# USBPowerSupply.net
KiCad netlist of a schematic drawn in EAGLE
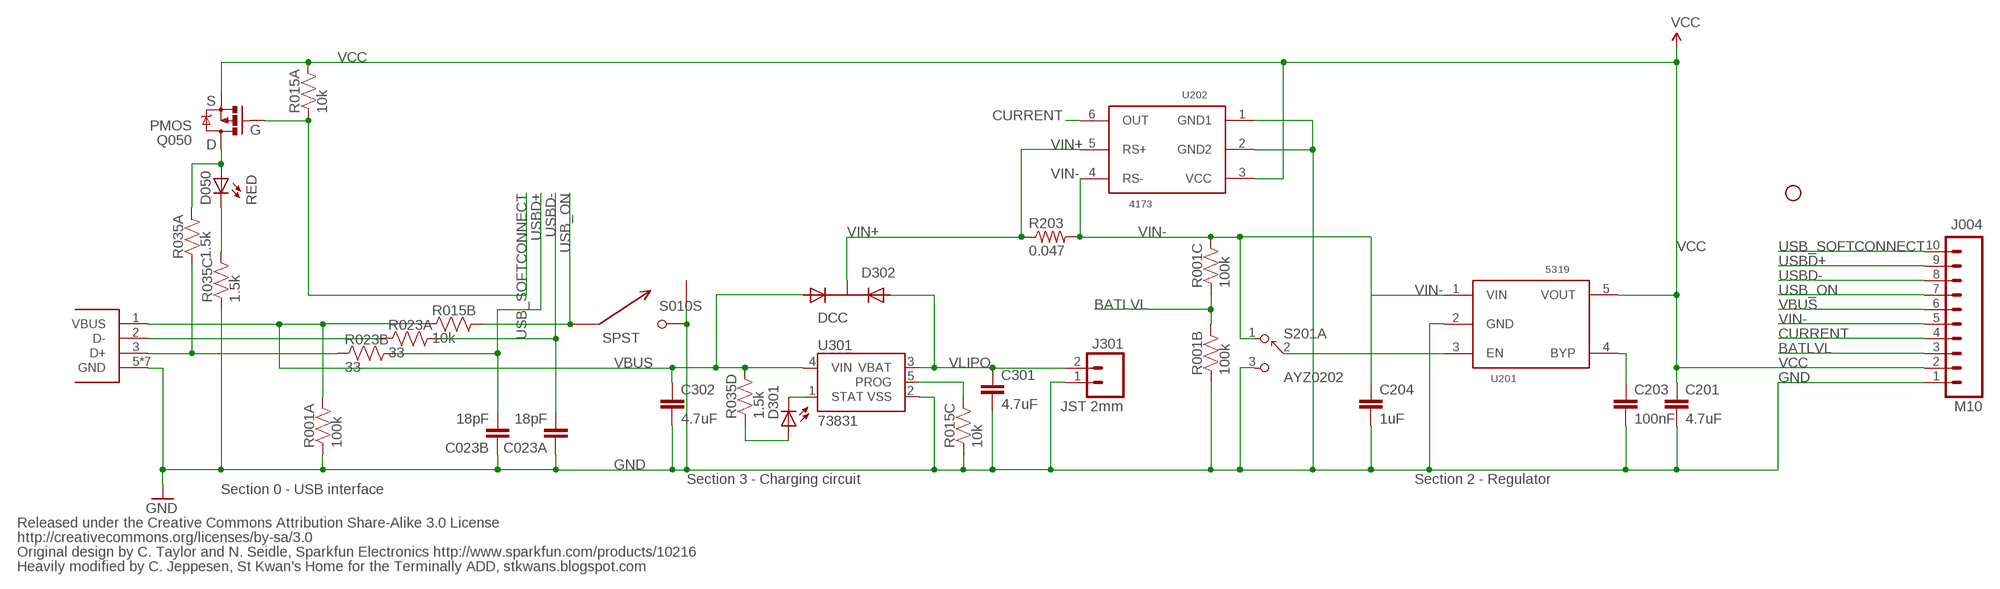
[diagram p0: schematic, sheet 1]

(export (version "E")
  (design (tool "Eeschema 10.0.6"))
  (components
    (comp (ref "C023")
      (value "18pF")
      (footprint "eagle-import:CKCM25")
      (libsource (lib "eagle-import") (part "CKCM25"))
    )
    (comp (ref "C201")
      (value "4.7uF")
      (footprint "eagle-import:0402-CAP")
      (libsource (lib "eagle-import") (part "CAP0402-CAP"))
    )
    (comp (ref "C203")
      (value "100nF")
      (footprint "eagle-import:0402-CAP")
      (libsource (lib "eagle-import") (part "CAP0402-CAP"))
    )
    (comp (ref "C204")
      (value "1uF")
      (footprint "eagle-import:0402-CAP")
      (libsource (lib "eagle-import") (part "CAP0402-CAP"))
    )
    (comp (ref "C301")
      (value "4.7uF")
      (footprint "eagle-import:0402-CAP")
      (libsource (lib "eagle-import") (part "CAP0402-CAP"))
    )
    (comp (ref "C302")
      (value "4.7uF")
      (footprint "eagle-import:0402-CAP")
      (libsource (lib "eagle-import") (part "CAP0402-CAP"))
    )
    (comp (ref "D050")
      (value "RED")
      (footprint "eagle-import:LED-0603")
      (libsource (lib "eagle-import") (part "LED0603"))
    )
    (comp (ref "D301")
      (value "RED")
      (footprint "eagle-import:LED-0603")
      (libsource (lib "eagle-import") (part "LED0603"))
    )
    (comp (ref "D302")
      (value "DCC")
      (footprint "eagle-import:SOT-23-3")
      (libsource (lib "eagle-import") (part "PMEG2005CT"))
    )
    (comp (ref "J001")
      (value "USB_MICROB_JSTGCT")
      (footprint "eagle-import:USB_MICROB_3075")
      (libsource (lib "eagle-import") (part "USB_MICROB_JSTGCT"))
    )
    (comp (ref "J004")
      (value "M10")
      (footprint "eagle-import:1X10")
      (libsource (lib "eagle-import") (part "M10{dblquote}"))
    )
    (comp (ref "J301")
      (value "JST 2mm")
      (footprint "eagle-import:JST-2-SMD")
      (libsource (lib "eagle-import") (part "M02-JST-2MM-SMT"))
    )
    (comp (ref "JP1")
      (value "STAND-OFF")
      (footprint "eagle-import:STAND-OFF")
      (libsource (lib "eagle-import") (part "STAND-OFF"))
    )
    (comp (ref "Q050")
      (value "PMOS")
      (footprint "eagle-import:SOT23-3")
      (libsource (lib "eagle-import") (part "MOSFET-PCHANNELSMD"))
    )
    (comp (ref "R001")
      (value "100k")
      (footprint "eagle-import:CRA04")
      (libsource (lib "eagle-import") (part "RP404"))
    )
    (comp (ref "R015")
      (value "10k")
      (footprint "eagle-import:CRA04")
      (libsource (lib "eagle-import") (part "RP404"))
    )
    (comp (ref "R023")
      (value "33")
      (footprint "eagle-import:CRA02")
      (libsource (lib "eagle-import") (part "RP2EXB24V"))
    )
    (comp (ref "R035")
      (value "1.5k")
      (footprint "eagle-import:CRA04")
      (libsource (lib "eagle-import") (part "RP404"))
    )
    (comp (ref "R203")
      (value "0.047")
      (footprint "eagle-import:0402-RES")
      (libsource (lib "eagle-import") (part "RESISTOR0402-RES"))
    )
    (comp (ref "S010")
      (value "SPST")
      (footprint "eagle-import:B3U-1100P")
      (libsource (lib "eagle-import") (part "B3U-1100P"))
    )
    (comp (ref "S201")
      (value "AYZ0202")
      (footprint "eagle-import:AYZ0202")
      (libsource (lib "eagle-import") (part "AYZ0202"))
    )
    (comp (ref "U201")
      (value "5319")
      (footprint "eagle-import:SOT-23-5")
      (libsource (lib "eagle-import") (part "MIC5319D5"))
    )
    (comp (ref "U202")
      (value "4173")
      (footprint "eagle-import:SOT-23-6")
      (libsource (lib "eagle-import") (part "MAX4173"))
    )
    (comp (ref "U301")
      (value "73831")
      (footprint "eagle-import:SOT23-5")
      (libsource (lib "eagle-import") (part "MCP73831"))
    )
  )
  (nets
    (net (code "1") (name "/BATLVL") (class "Default")
      (node (ref "J004") (pin "3") (pinfunction "3_3") (pintype "passive"))
      (node (ref "R001") (pin "3") (pinfunction "1_3") (pintype "passive"))
      (node (ref "R001") (pin "7") (pinfunction "2_7") (pintype "passive"))
    )
    (net (code "2") (name "/CURRENT") (class "Default")
      (node (ref "J004") (pin "4") (pinfunction "4_4") (pintype "passive"))
      (node (ref "U202") (pin "6") (pinfunction "OUT_6") (pintype "bidirectional"))
    )
    (net (code "3") (name "/USBD+") (class "Default")
      (node (ref "C023") (pin "3") (pinfunction "2_3") (pintype "passive"))
      (node (ref "J004") (pin "9") (pinfunction "9_9") (pintype "passive"))
      (node (ref "R023") (pin "3") (pinfunction "2_3") (pintype "passive"))
    )
    (net (code "4") (name "/USBD-") (class "Default")
      (node (ref "C023") (pin "4") (pinfunction "2_4") (pintype "passive"))
      (node (ref "J004") (pin "8") (pinfunction "8_8") (pintype "passive"))
      (node (ref "R023") (pin "4") (pinfunction "2_4") (pintype "passive"))
    )
    (net (code "5") (name "/USB_ON") (class "Default")
      (node (ref "J004") (pin "7") (pinfunction "7_7") (pintype "passive"))
      (node (ref "R015") (pin "7") (pinfunction "2_7") (pintype "passive"))
      (node (ref "S010") (pin "P$1") (pinfunction "1_P$1") (pintype "bidirectional"))
    )
    (net (code "6") (name "/USB_SOFTCONNECT") (class "Default")
      (node (ref "J004") (pin "10") (pinfunction "10_10") (pintype "passive"))
      (node (ref "Q050") (pin "1") (pinfunction "G_1") (pintype "passive"))
      (node (ref "R015") (pin "1") (pinfunction "1_1") (pintype "passive"))
    )
    (net (code "7") (name "/VBUS") (class "Default")
      (node (ref "C302") (pin "1") (pinfunction "1_1") (pintype "passive"))
      (node (ref "D302") (pin "1") (pinfunction "A1_1") (pintype "passive"))
      (node (ref "J001") (pin "1") (pinfunction "VBUS_1") (pintype "bidirectional"))
      (node (ref "J004") (pin "6") (pinfunction "6_6") (pintype "passive"))
      (node (ref "R001") (pin "8") (pinfunction "2_8") (pintype "passive"))
      (node (ref "R015") (pin "2") (pinfunction "1_2") (pintype "passive"))
      (node (ref "R035") (pin "5") (pinfunction "2_5") (pintype "passive"))
      (node (ref "U301") (pin "4") (pinfunction "VIN_4") (pintype "power_in"))
    )
    (net (code "8") (name "/VIN+") (class "Default")
      (node (ref "D302") (pin "3") (pinfunction "K_3") (pintype "passive"))
      (node (ref "R203") (pin "1") (pinfunction "1_1") (pintype "passive"))
      (node (ref "U202") (pin "5") (pinfunction "RS+_5") (pintype "bidirectional"))
    )
    (net (code "9") (name "/VIN-") (class "Default")
      (node (ref "C204") (pin "1") (pinfunction "1_1") (pintype "passive"))
      (node (ref "J004") (pin "5") (pinfunction "5_5") (pintype "passive"))
      (node (ref "R001") (pin "6") (pinfunction "2_6") (pintype "passive"))
      (node (ref "R203") (pin "2") (pinfunction "2_2") (pintype "passive"))
      (node (ref "S201") (pin "1") (pinfunction "P$1_1") (pintype "bidirectional"))
      (node (ref "U201") (pin "1") (pinfunction "VIN_1") (pintype "bidirectional"))
      (node (ref "U202") (pin "4") (pinfunction "RS-_4") (pintype "bidirectional"))
    )
    (net (code "10") (name "/VLIPO") (class "Default")
      (node (ref "C301") (pin "1") (pinfunction "1_1") (pintype "passive"))
      (node (ref "D302") (pin "2") (pinfunction "A2_2") (pintype "passive"))
      (node (ref "J301") (pin "2") (pinfunction "2_2") (pintype "passive"))
      (node (ref "U301") (pin "3") (pinfunction "VBAT_3") (pintype "power_in"))
    )
    (net (code "11") (name "GND") (class "Default")
      (node (ref "C023") (pin "1") (pinfunction "1_1") (pintype "passive"))
      (node (ref "C023") (pin "2") (pinfunction "1_2") (pintype "passive"))
      (node (ref "C201") (pin "2") (pinfunction "2_2") (pintype "passive"))
      (node (ref "C203") (pin "2") (pinfunction "2_2") (pintype "passive"))
      (node (ref "C204") (pin "2") (pinfunction "2_2") (pintype "passive"))
      (node (ref "C301") (pin "2") (pinfunction "2_2") (pintype "passive"))
      (node (ref "C302") (pin "2") (pinfunction "2_2") (pintype "passive"))
      (node (ref "J001") (pin "5") (pinfunction "GND_5") (pintype "bidirectional"))
      (node (ref "J001") (pin "P$1") (pinfunction "GND_P$1") (pintype "bidirectional"))
      (node (ref "J001") (pin "P$10") (pinfunction "GND_P$10") (pintype "bidirectional"))
      (node (ref "J001") (pin "P$2") (pinfunction "GND_P$2") (pintype "bidirectional"))
      (node (ref "J001") (pin "P$3") (pinfunction "GND_P$3") (pintype "bidirectional"))
      (node (ref "J001") (pin "P$4") (pinfunction "GND_P$4") (pintype "bidirectional"))
      (node (ref "J001") (pin "P$8") (pinfunction "GND_P$8") (pintype "bidirectional"))
      (node (ref "J004") (pin "1") (pinfunction "1_1") (pintype "passive"))
      (node (ref "J301") (pin "1") (pinfunction "1_1") (pintype "passive"))
      (node (ref "R001") (pin "1") (pinfunction "1_1") (pintype "passive"))
      (node (ref "R001") (pin "2") (pinfunction "1_2") (pintype "passive"))
      (node (ref "R015") (pin "3") (pinfunction "1_3") (pintype "passive"))
      (node (ref "R035") (pin "3") (pinfunction "1_3") (pintype "passive"))
      (node (ref "S010") (pin "P$2") (pinfunction "2_P$2") (pintype "bidirectional"))
      (node (ref "S010") (pin "P$3") (pinfunction "1_P$3") (pintype "bidirectional"))
      (node (ref "S201") (pin "3") (pinfunction "P$2_3") (pintype "bidirectional"))
      (node (ref "U201") (pin "2") (pinfunction "GND_2") (pintype "bidirectional"))
      (node (ref "U202") (pin "1") (pinfunction "GND1_1") (pintype "bidirectional"))
      (node (ref "U202") (pin "2") (pinfunction "GND2_2") (pintype "bidirectional"))
      (node (ref "U301") (pin "2") (pinfunction "VSS_2") (pintype "power_in"))
    )
    (net (code "12") (name "Net-(J001-D+)") (class "Default")
      (node (ref "J001") (pin "3") (pinfunction "D+_3") (pintype "bidirectional"))
      (node (ref "R023") (pin "2") (pinfunction "1_2") (pintype "passive"))
      (node (ref "R035") (pin "1") (pinfunction "1_1") (pintype "passive"))
    )
    (net (code "13") (name "Net-(J001-D-)") (class "Default")
      (node (ref "J001") (pin "2") (pinfunction "D-_2") (pintype "bidirectional"))
      (node (ref "R023") (pin "1") (pinfunction "1_1") (pintype "passive"))
    )
    (net (code "14") (name "Net-(Q050-D)") (class "Default")
      (node (ref "D050") (pin "A") (pinfunction "A_A") (pintype "passive"))
      (node (ref "Q050") (pin "3") (pinfunction "D_3") (pintype "passive"))
      (node (ref "R035") (pin "8") (pinfunction "2_8") (pintype "passive"))
    )
    (net (code "15") (name "Net-(R015C-2)") (class "Default")
      (node (ref "R015") (pin "6") (pinfunction "2_6") (pintype "passive"))
      (node (ref "U301") (pin "5") (pinfunction "PROG_5") (pintype "input"))
    )
    (net (code "16") (name "Net-(R035C-2)") (class "Default")
      (node (ref "D050") (pin "C") (pinfunction "C_C") (pintype "passive"))
      (node (ref "R035") (pin "6") (pinfunction "2_6") (pintype "passive"))
    )
    (net (code "17") (name "Net-(R035D-1)") (class "Default")
      (node (ref "D301") (pin "A") (pinfunction "A_A") (pintype "passive"))
      (node (ref "R035") (pin "4") (pinfunction "1_4") (pintype "passive"))
    )
    (net (code "18") (name "Net-(S201A-P$3)") (class "Default")
      (node (ref "S201") (pin "2") (pinfunction "P$3_2") (pintype "bidirectional"))
      (node (ref "U201") (pin "3") (pinfunction "EN_3") (pintype "bidirectional"))
    )
    (net (code "19") (name "Net-(U201-BYP)") (class "Default")
      (node (ref "C203") (pin "1") (pinfunction "1_1") (pintype "passive"))
      (node (ref "U201") (pin "4") (pinfunction "BYP_4") (pintype "bidirectional"))
    )
    (net (code "20") (name "Net-(U301-STAT)") (class "Default")
      (node (ref "D301") (pin "C") (pinfunction "C_C") (pintype "passive"))
      (node (ref "U301") (pin "1") (pinfunction "STAT_1") (pintype "output"))
    )
    (net (code "21") (name "VCC") (class "Default")
      (node (ref "C201") (pin "1") (pinfunction "1_1") (pintype "passive"))
      (node (ref "J004") (pin "2") (pinfunction "2_2") (pintype "passive"))
      (node (ref "Q050") (pin "2") (pinfunction "S_2") (pintype "passive"))
      (node (ref "R015") (pin "8") (pinfunction "2_8") (pintype "passive"))
      (node (ref "U201") (pin "5") (pinfunction "VOUT_5") (pintype "bidirectional"))
      (node (ref "U202") (pin "3") (pinfunction "VCC_3") (pintype "bidirectional"))
    )
  )
)
